# G_ve_Koruma.net
KiCad netlist of a schematic drawn in Altium Designer
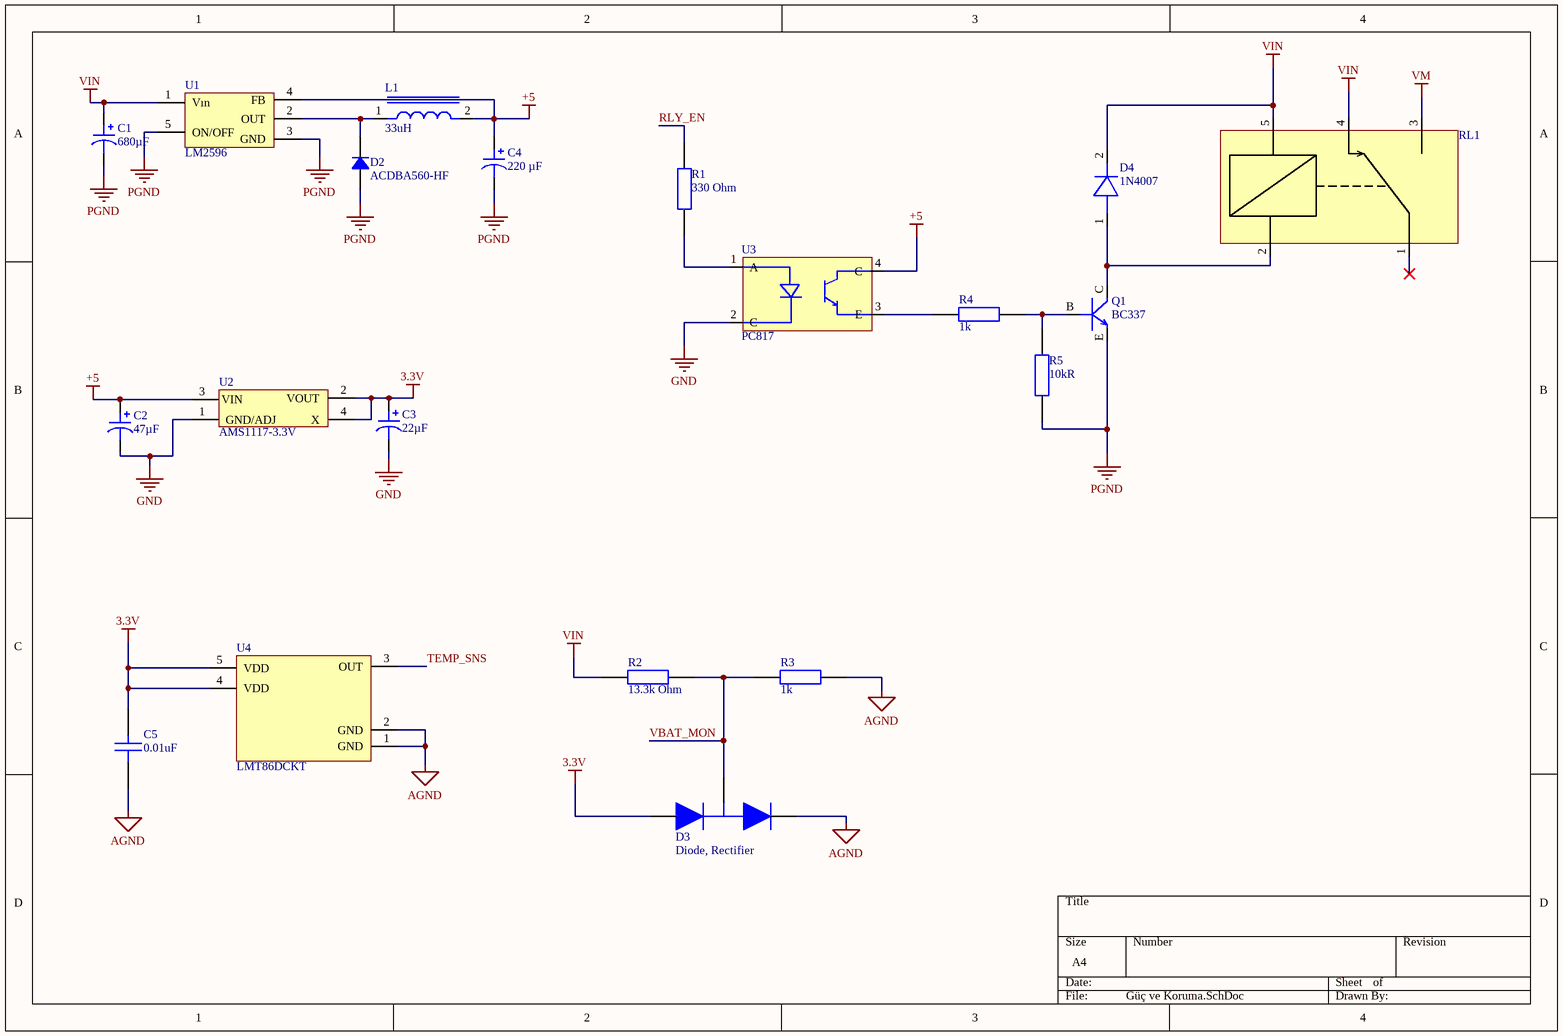
[diagram p0: Güç ve Koruma.SchDoc]

(export (version "E")
  (design (tool "Eeschema 10.0.6"))
  (components
    (comp (ref "C1")
      (value "680µF")
      (footprint "CAP TH ALUM ELEC D12.50mm S5.00mm H30.00mm")
      (description "CAP ALUM 680UF 20% 50V RADIAL")
      (fields
        (field (name "PART NUMBER") "EEU-FC1H681L")
        (field (name "MANUFACTURER") "Panasonic Electronic Components")
      )
      (libsource (lib "Celestial Altium Library - altium_library") (part "Polarised Capacitor"))
    )
    (comp (ref "C2")
      (value "47µF")
      (footprint "CAP TH ALUM ELEC D6.30mm S2.50mm H6.00mm")
      (description "CAP ALUM 47UF 20% 16V RADIAL")
      (fields (field (name "PART NUMBER") "UMF1C470MDD") (field (name "MANUFACTURER") "Nichicon"))
      (libsource (lib "") (part "Polarised Capacitor_1"))
    )
    (comp (ref "C3")
      (value "22µF")
      (footprint "CAP TH ALUM ELEC D6.30mm S2.50mm H12.00mm")
      (description "CAP ALUM 22UF 20% 16V RADIAL")
      (fields (field (name "PART NUMBER") "UES1C220MEM1TD") (field (name "MANUFACTURER") "Nichicon"))
      (libsource (lib "Celestial Altium Library - altium_library") (part "Polarised Capacitor"))
    )
    (comp (ref "C4")
      (value "220 µF")
      (footprint "CAP AL TH D8 L3.5 H12.5")
      (description "CAP ALUM 220UF 20% 25V RADIAL")
      (fields (field (name "PART NUMBER") "ESW227M025AG3AA") (field (name "MANUFACTURER") "KEMET"))
      (libsource (lib "Celestial Altium Library - altium_library") (part "Polarised Capacitor"))
    )
    (comp (ref "C5")
      (value "0.01uF")
      (footprint "CAP0603- GRM188R70J103KA01D")
      (description "CAP CER 10000PF 6.3V X7R 0603")
      (fields (field (name "TOLERANCE") "±10%") (field (name "MANUFACTURER") "Murata"))
      (libsource (lib "TIDA_00620") (part "GRM188R70J103KA01D"))
    )
    (comp (ref "D2")
      (value "ACDBA560-HF")
      (footprint "DO214AC SMA")
      (description "DIODE SCHOTTKY 60V 5A DO214AC")
      (fields (field (name "MANUFACTURER") "Comchip Technology"))
      (libsource (lib "Celestial Altium Library - altium_library") (part "Diode"))
    )
    (comp (ref "D3")
      (value "Diode, Rectifier")
      (footprint "SOT-23-3 - MMBD7000LT1G")
      (description "Diode, Rectifier, Switching, Vr 100VDC, If 200MA, Pkg SOT-23 (TO-236AB), Config Dual")
      (fields (field (name "MANUFACTURER") "onsemi") (field (name "MANUFACTURER PART NUMBER") "MMBD7000LT1G"))
      (libsource (lib "TIDA_00620") (part "MMBD7000LT1G"))
    )
    (comp (ref "D4")
      (value "1N4007")
      (footprint "1N4007")
      (description "Rectifier Diode, 1 Phase, 1 Element, 1A, 1000V V(RRM), Silicon, DO-204AC")
      (fields (field (name "MANUFACTURER") "Diotec"))
      (libsource (lib "TIDA_00620") (part "1N4007"))
    )
    (comp (ref "L1")
      (value "33uH")
      (footprint "Cap33Uh")
      (description "Inductor Power Shielded Wirewound 33uH 20% 1KHz 27Q-Factor Ferrite 3A 60mOhm DCR T/R")
      (fields (field (name "MANUFACTURER") "Bourns") (field (name "MANUFACTURER PART NUMBER") "SRR1260-330M"))
      (libsource (lib "TIDA_00620") (part "CAP33uH"))
    )
    (comp (ref "Q1")
      (value "BC337")
      (footprint "BC337")
      (description "Small Signal Bipolar Transistor, 0.8A I(C), 45V V(BR)CEO, 1-Element, NPN, Silicon, TO-92")
      (fields (field (name "MANUFACTURER") "onsemi") (field (name "MANUFACTURER PART NUMBER") "BC33725TA"))
      (libsource (lib "TIDA_00620") (part "BC337"))
    )
    (comp (ref "R1")
      (value "330 Ohm")
      (footprint "RES0603- RC0603FR-07330RL")
      (description "Res Thick Film 0603 330 Ohm 1% 0.1W(1/10W) ±100ppm/C Pad SMD T/R")
      (fields
        (field (name "MANUFACTURER") "Yageo Group")
        (field (name "MANUFACTURER PART NUMBER") "RC0603FR-07330RL")
      )
      (libsource (lib "TIDA_00620") (part "RC0603FR-07330RL"))
    )
    (comp (ref "R2")
      (value "13.3k Ohm")
      (footprint "RES0402")
      (description "CRCW FIXED RESISTOR 0402 (1005Metric) Chip Resistor ±1% ±100ppm/C 13.3kOhm 0.063W 1/16W")
      (fields
        (field (name "MANUFACTURER") "Vishay")
        (field (name "MANUFACTURER PART NUMBER") "CRCW040213K3FKED")
      )
      (libsource (lib "TIDA_00620") (part "CRCW040213K3FKED"))
    )
    (comp (ref "R3")
      (value "1k")
      (footprint "RES0402")
      (description "Res Thick Film 0402 1K Ohm 1% 1/16W ±100ppm/°C Molded SMD Paper T/R")
      (fields
        (field (name "MANUFACTURER") "Vishay")
        (field (name "MANUFACTURER PART NUMBER") "CRCW04021K00FKED")
      )
      (libsource (lib "TIDA_00620") (part "CRCW04021K00FKED"))
    )
    (comp (ref "R4")
      (value "1k")
      (footprint "RES0402")
      (description "Res Thick Film 0402 1K Ohm 1% 1/16W ±100ppm/°C Molded SMD Paper T/R")
      (fields
        (field (name "MANUFACTURER") "Vishay")
        (field (name "MANUFACTURER PART NUMBER") "CRCW04021K00FKED")
      )
      (libsource (lib "TIDA_00620") (part "CRCW04021K00FKED"))
    )
    (comp (ref "R5")
      (value "RC0603FR-0710KL")
      (footprint "RES_0603")
      (description "RES 10K %1 OHM 0603 SMD")
      (fields
        (field (name "MANUFACTURER") "Yageo")
        (field (name "TOLERANCE") "1%")
        (field (name "RESISTANCE") "10kR")
        (field (name "DESIGNED BY") "BERK")
      )
      (libsource (lib "UDEMY_Library") (part "RES 10K OHM 0603"))
    )
    (comp (ref "RL1")
      (value "HK15F-DC24V-S-K")
      (footprint "HK15F-DC24V-S-K")
      (description "24V 30A Amperli T Röle HK15F-DC24V-S-K")
      (libsource (lib "TIDA_00620") (part "HK15F-DC24V-S-K"))
    )
    (comp (ref "U1")
      (value "LM2596")
      (footprint "LM2596")
      (description "Conv DC-DC 4.5V to 40V Step Down Single-Out 1.23V to 37V 3A 6-Pin(5+Tab) D2PAK Tube")
      (fields (field (name "MANUFACTURER") "onsemi") (field (name "MANUFACTURER PART NUMBER") "LM2596DSADJG"))
      (libsource (lib "TIDA_00620") (part "LM2596"))
    )
    (comp (ref "U2")
      (value "AMS1117-3.3V")
      (footprint "SOT223")
      (libsource (lib "TIDA_00620") (part "AMS1117-3.3V"))
    )
    (comp (ref "U3")
      (value "PC817")
      (footprint "PC817")
      (description "Optocoupler DC-IN 1-CH Transistor DC-OUT 4-Pin PDIP Sleeve")
      (fields (field (name "MANUFACTURER") "Sharp") (field (name "MANUFACTURER PART NUMBER") "PC817X1J000F"))
      (libsource (lib "TIDA_00620") (part "PC817"))
    )
    (comp (ref "U4")
      (value "LMT86DCKT")
      (footprint "LMT86DCKT")
      (description "2.2V-Capable, 10 uA Analog Output Temperature Sensor in SC70 and TO-92 5-SC70 -50 to 150")
      (fields (field (name "MANUFACTURER") "Texas Instruments"))
      (libsource (lib "TIDA_00620") (part "LMT86DCKT"))
    )
  )
  (nets
    (net (code "1") (name "+5") (class "Default")
      (node (ref "C2") (pin "1") (pinfunction "1_1") (pintype "passive"))
      (node (ref "C4") (pin "1") (pinfunction "1_1") (pintype "passive"))
      (node (ref "L1") (pin "2") (pintype "passive"))
      (node (ref "U1") (pin "4") (pinfunction "FB_4") (pintype "passive"))
      (node (ref "U2") (pin "3") (pinfunction "VIN_3") (pintype "passive"))
      (node (ref "U3") (pin "4") (pinfunction "C_4") (pintype "passive"))
    )
    (net (code "2") (name "/RLY_EN") (class "Default")
      (node (ref "R1") (pin "1") (pinfunction "1_1") (pintype "passive"))
    )
    (net (code "3") (name "/TEMP_SNS") (class "Default")
      (node (ref "U4") (pin "3") (pinfunction "OUT_3") (pintype "passive"))
    )
    (net (code "4") (name "/VBAT_MON") (class "Default")
      (node (ref "D3") (pin "3") (pinfunction "3_3") (pintype "passive"))
      (node (ref "R2") (pin "2") (pinfunction "2_2") (pintype "passive"))
      (node (ref "R3") (pin "1") (pinfunction "1_1") (pintype "passive"))
    )
    (net (code "5") (name "3.3V") (class "Default")
      (node (ref "C3") (pin "1") (pinfunction "1_1") (pintype "passive"))
      (node (ref "C5") (pin "2") (pinfunction "2_2") (pintype "passive"))
      (node (ref "D3") (pin "1") (pinfunction "1_1") (pintype "passive"))
      (node (ref "U2") (pin "2") (pinfunction "VOUT_2") (pintype "passive"))
      (node (ref "U2") (pin "4") (pinfunction "X_4") (pintype "passive"))
      (node (ref "U4") (pin "4") (pinfunction "VDD_4") (pintype "power_in"))
      (node (ref "U4") (pin "5") (pinfunction "VDD_5") (pintype "power_in"))
    )
    (net (code "6") (name "AGND") (class "Default")
      (node (ref "C5") (pin "1") (pinfunction "1_1") (pintype "passive"))
      (node (ref "D3") (pin "2") (pinfunction "2_2") (pintype "passive"))
      (node (ref "R3") (pin "2") (pinfunction "2_2") (pintype "passive"))
      (node (ref "U4") (pin "1") (pinfunction "GND_1") (pintype "power_in"))
      (node (ref "U4") (pin "2") (pinfunction "GND_2") (pintype "power_in"))
    )
    (net (code "7") (name "GND") (class "Default")
      (node (ref "C2") (pin "2") (pinfunction "2_2") (pintype "passive"))
      (node (ref "C3") (pin "2") (pinfunction "2_2") (pintype "passive"))
      (node (ref "U2") (pin "1") (pinfunction "GND/ADJ_1") (pintype "passive"))
      (node (ref "U3") (pin "2") (pinfunction "C_2") (pintype "passive"))
    )
    (net (code "8") (name "Net-(D4-Pad1)") (class "Default")
      (node (ref "D4") (pin "1") (pintype "passive"))
      (node (ref "Q1") (pin "C") (pintype "passive"))
      (node (ref "RL1") (pin "2") (pintype "passive"))
    )
    (net (code "9") (name "Net-(Q1-PadB)") (class "Default")
      (node (ref "Q1") (pin "B") (pintype "passive"))
      (node (ref "R4") (pin "2") (pinfunction "2_2") (pintype "passive"))
      (node (ref "R5") (pin "1") (pinfunction "1_1") (pintype "passive"))
    )
    (net (code "10") (name "Net-(U1-OUT)") (class "Default")
      (node (ref "D2") (pin "2") (pinfunction "2_2") (pintype "passive"))
      (node (ref "L1") (pin "1") (pintype "passive"))
      (node (ref "U1") (pin "2") (pinfunction "OUT_2") (pintype "passive"))
    )
    (net (code "11") (name "Net-(U3-A)") (class "Default")
      (node (ref "R1") (pin "2") (pinfunction "2_2") (pintype "passive"))
      (node (ref "U3") (pin "1") (pinfunction "A_1") (pintype "passive"))
    )
    (net (code "12") (name "Net-(U3-E)") (class "Default")
      (node (ref "R4") (pin "1") (pinfunction "1_1") (pintype "passive"))
      (node (ref "U3") (pin "3") (pinfunction "E_3") (pintype "passive"))
    )
    (net (code "13") (name "PGND") (class "Default")
      (node (ref "C1") (pin "2") (pinfunction "2_2") (pintype "passive"))
      (node (ref "C4") (pin "2") (pinfunction "2_2") (pintype "passive"))
      (node (ref "D2") (pin "1") (pinfunction "1_1") (pintype "passive"))
      (node (ref "Q1") (pin "E") (pintype "passive"))
      (node (ref "R5") (pin "2") (pinfunction "2_2") (pintype "passive"))
      (node (ref "U1") (pin "3") (pinfunction "GND_3") (pintype "passive"))
      (node (ref "U1") (pin "5") (pinfunction "ON/OFF_5") (pintype "passive"))
    )
    (net (code "14") (name "VIN") (class "Default")
      (node (ref "C1") (pin "1") (pinfunction "1_1") (pintype "passive"))
      (node (ref "D4") (pin "2") (pintype "passive"))
      (node (ref "R2") (pin "1") (pinfunction "1_1") (pintype "passive"))
      (node (ref "RL1") (pin "4") (pintype "passive"))
      (node (ref "RL1") (pin "5") (pintype "passive"))
      (node (ref "U1") (pin "1") (pinfunction "Vın_1") (pintype "passive"))
    )
    (net (code "15") (name "VM") (class "Default") (node (ref "RL1") (pin "3") (pintype "passive")))
    (net (code "16") (name "unconnected-(RL1-Pad1)") (class "Default")
      (node (ref "RL1") (pin "1") (pintype "passive+no_connect"))
    )
  )
)
